# speaker.net
KiCad netlist of a schematic drawn in Altium Designer
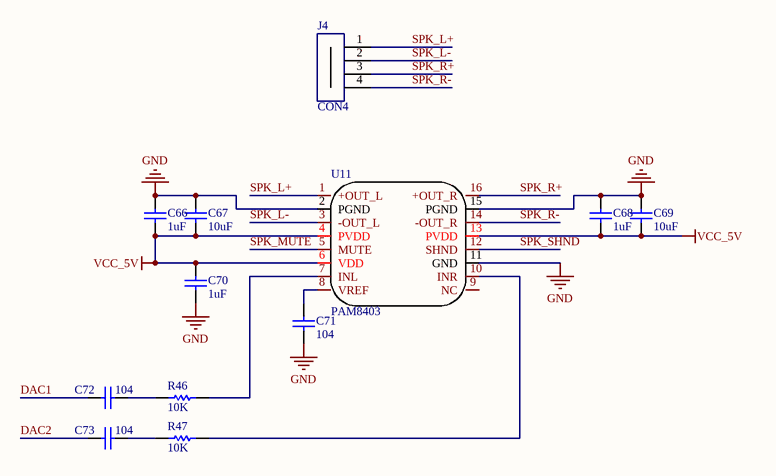
[diagram p0: speaker.SchDoc]

(export (version "E")
  (design (tool "Eeschema 10.0.6"))
  (components
    (comp (ref "C66") (value "1uF") (footprint "C 0603") (libsource (lib "Sheet") (part "CAP")))
    (comp (ref "C67") (value "10uF") (footprint "C 0603") (libsource (lib "Sheet") (part "CAP")))
    (comp (ref "C68") (value "1uF") (footprint "C 0603") (libsource (lib "Sheet") (part "CAP")))
    (comp (ref "C69") (value "10uF") (footprint "C 0603") (libsource (lib "Sheet") (part "CAP")))
    (comp (ref "C70") (value "1uF") (footprint "C 0603") (libsource (lib "Sheet") (part "CAP")))
    (comp (ref "C71") (value "104") (footprint "C 0603") (libsource (lib "Sheet") (part "CAP")))
    (comp (ref "C72") (value "104") (footprint "C 0603") (libsource (lib "Sheet") (part "CAP")))
    (comp (ref "C73") (value "104") (footprint "C 0603") (libsource (lib "Sheet") (part "CAP")))
    (comp (ref "J4") (value "CON4") (footprint "SMD_4P-1.25") (libsource (lib "Sheet") (part "CON4")))
    (comp (ref "R46") (value "10K") (footprint "R 0603") (libsource (lib "Sheet") (part "RES")))
    (comp (ref "R47") (value "10K") (footprint "R 0603") (libsource (lib "Sheet") (part "RES")))
    (comp (ref "U11") (value "PAM8403") (footprint "SOP-16") (libsource (lib "Sheet") (part "PAM8403")))
  )
  (nets
    (net (code "1") (name "/DAC1") (class "Default")
      (node (ref "C72") (pin "2") (pinfunction "2_2") (pintype "passive"))
    )
    (net (code "2") (name "/DAC2") (class "Default")
      (node (ref "C73") (pin "2") (pinfunction "2_2") (pintype "passive"))
    )
    (net (code "3") (name "/SPK_L+") (class "Default")
      (node (ref "J4") (pin "1") (pinfunction "1_1") (pintype "passive"))
      (node (ref "U11") (pin "1") (pinfunction "+OUT_L_1") (pintype "passive"))
    )
    (net (code "4") (name "/SPK_L-") (class "Default")
      (node (ref "J4") (pin "2") (pinfunction "2_2") (pintype "passive"))
      (node (ref "U11") (pin "3") (pinfunction "-OUT_L_3") (pintype "passive"))
    )
    (net (code "5") (name "/SPK_MUTE") (class "Default")
      (node (ref "U11") (pin "5") (pinfunction "MUTE_5") (pintype "passive"))
    )
    (net (code "6") (name "/SPK_R+") (class "Default")
      (node (ref "J4") (pin "3") (pinfunction "3_3") (pintype "passive"))
      (node (ref "U11") (pin "16") (pinfunction "+OUT_R_16") (pintype "passive"))
    )
    (net (code "7") (name "/SPK_R-") (class "Default")
      (node (ref "J4") (pin "4") (pinfunction "4_4") (pintype "passive"))
      (node (ref "U11") (pin "14") (pinfunction "-OUT_R_14") (pintype "passive"))
    )
    (net (code "8") (name "/SPK_SHND") (class "Default")
      (node (ref "U11") (pin "12") (pinfunction "SHND_12") (pintype "passive"))
    )
    (net (code "9") (name "GND") (class "Default")
      (node (ref "C66") (pin "2") (pinfunction "2_2") (pintype "passive"))
      (node (ref "C67") (pin "2") (pinfunction "2_2") (pintype "passive"))
      (node (ref "C68") (pin "2") (pinfunction "2_2") (pintype "passive"))
      (node (ref "C69") (pin "2") (pinfunction "2_2") (pintype "passive"))
      (node (ref "C70") (pin "1") (pinfunction "1_1") (pintype "passive"))
      (node (ref "C71") (pin "1") (pinfunction "1_1") (pintype "passive"))
      (node (ref "U11") (pin "11") (pinfunction "GND_11") (pintype "passive"))
      (node (ref "U11") (pin "15") (pinfunction "PGND_15") (pintype "passive"))
      (node (ref "U11") (pin "2") (pinfunction "PGND_2") (pintype "passive"))
    )
    (net (code "10") (name "Net-(C72-Pad1)") (class "Default")
      (node (ref "C72") (pin "1") (pinfunction "1_1") (pintype "passive"))
      (node (ref "R46") (pin "1") (pinfunction "1_1") (pintype "passive"))
    )
    (net (code "11") (name "Net-(C73-Pad1)") (class "Default")
      (node (ref "C73") (pin "1") (pinfunction "1_1") (pintype "passive"))
      (node (ref "R47") (pin "1") (pinfunction "1_1") (pintype "passive"))
    )
    (net (code "12") (name "Net-(U11-INL)") (class "Default")
      (node (ref "R46") (pin "2") (pinfunction "2_2") (pintype "passive"))
      (node (ref "U11") (pin "7") (pinfunction "INL_7") (pintype "passive"))
    )
    (net (code "13") (name "Net-(U11-INR)") (class "Default")
      (node (ref "R47") (pin "2") (pinfunction "2_2") (pintype "passive"))
      (node (ref "U11") (pin "10") (pinfunction "INR_10") (pintype "passive"))
    )
    (net (code "14") (name "Net-(U11-VREF)") (class "Default")
      (node (ref "C71") (pin "2") (pinfunction "2_2") (pintype "passive"))
      (node (ref "U11") (pin "8") (pinfunction "VREF_8") (pintype "passive"))
    )
    (net (code "15") (name "VCC_5V") (class "Default")
      (node (ref "C66") (pin "1") (pinfunction "1_1") (pintype "passive"))
      (node (ref "C67") (pin "1") (pinfunction "1_1") (pintype "passive"))
      (node (ref "C68") (pin "1") (pinfunction "1_1") (pintype "passive"))
      (node (ref "C69") (pin "1") (pinfunction "1_1") (pintype "passive"))
      (node (ref "C70") (pin "2") (pinfunction "2_2") (pintype "passive"))
      (node (ref "U11") (pin "13") (pinfunction "PVDD_13") (pintype "passive"))
      (node (ref "U11") (pin "4") (pinfunction "PVDD_4") (pintype "passive"))
      (node (ref "U11") (pin "6") (pinfunction "VDD_6") (pintype "passive"))
    )
    (net (code "16") (name "unconnected-(U11-NC-Pad9)") (class "Default")
      (node (ref "U11") (pin "9") (pinfunction "NC_9") (pintype "passive"))
    )
  )
)
